# 1-Schematic_ESC36V_2_0.net
KiCad netlist of a schematic drawn in EasyEDA
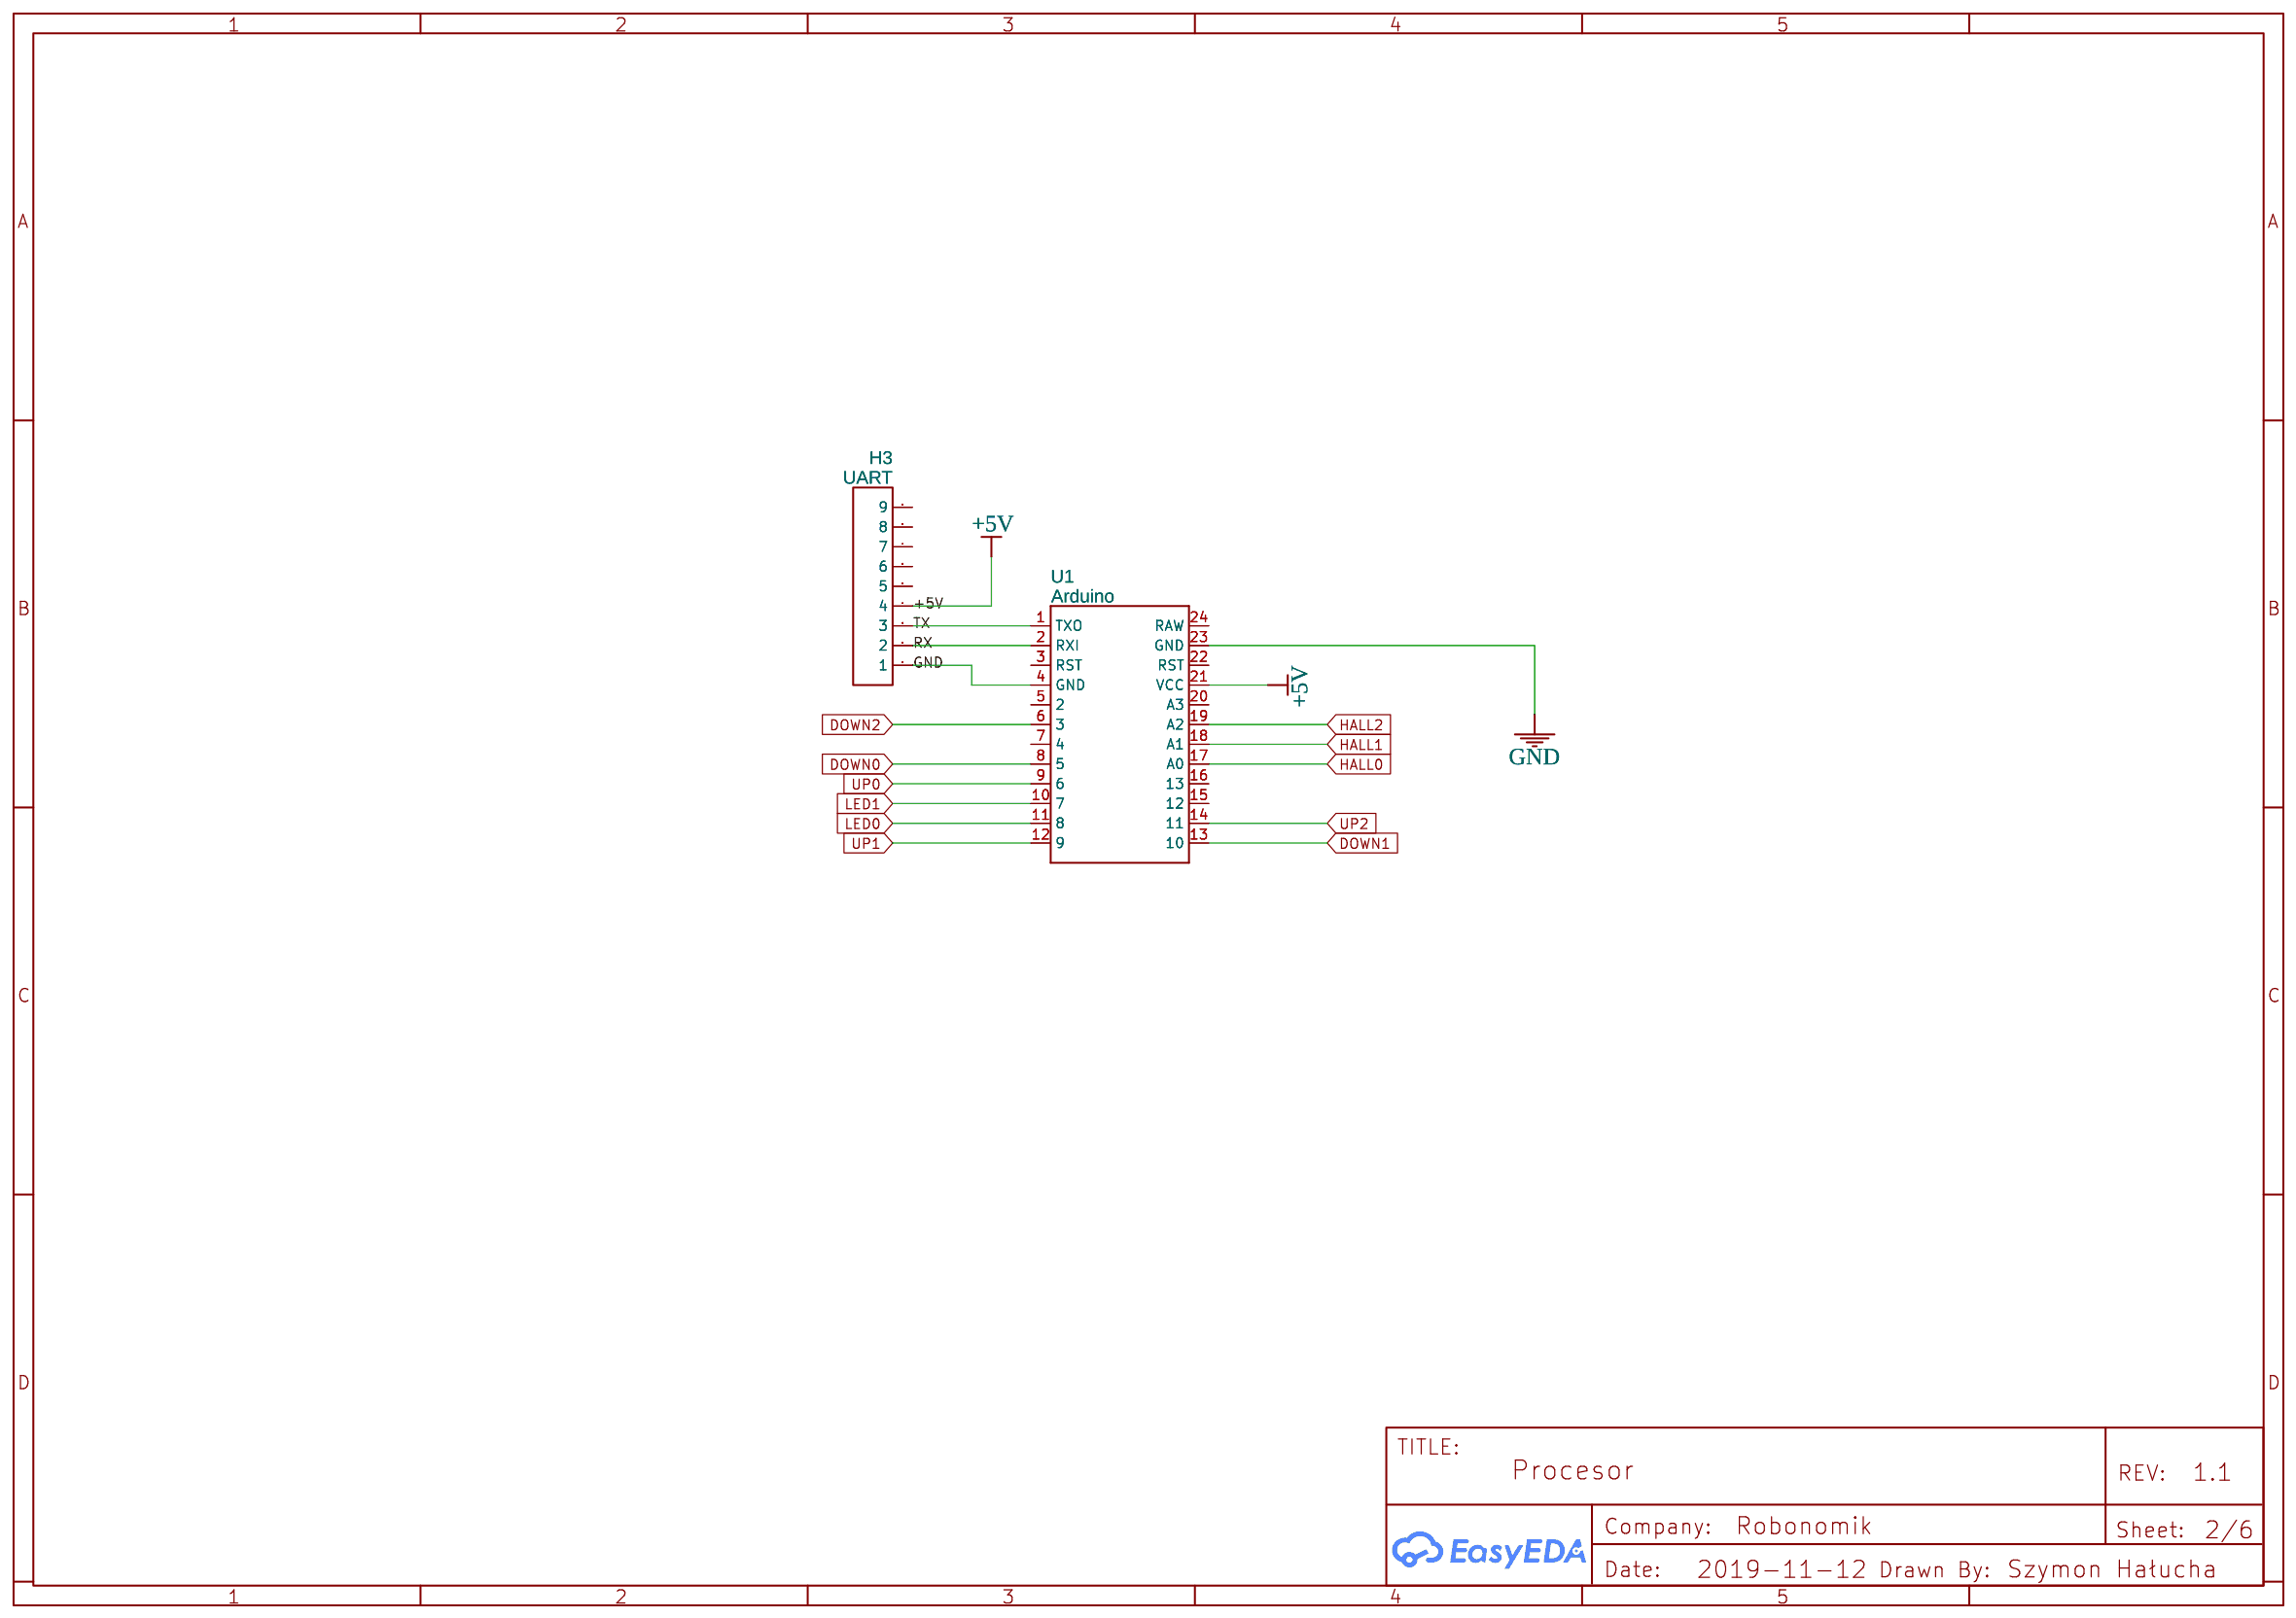
[diagram p0: Procesor]
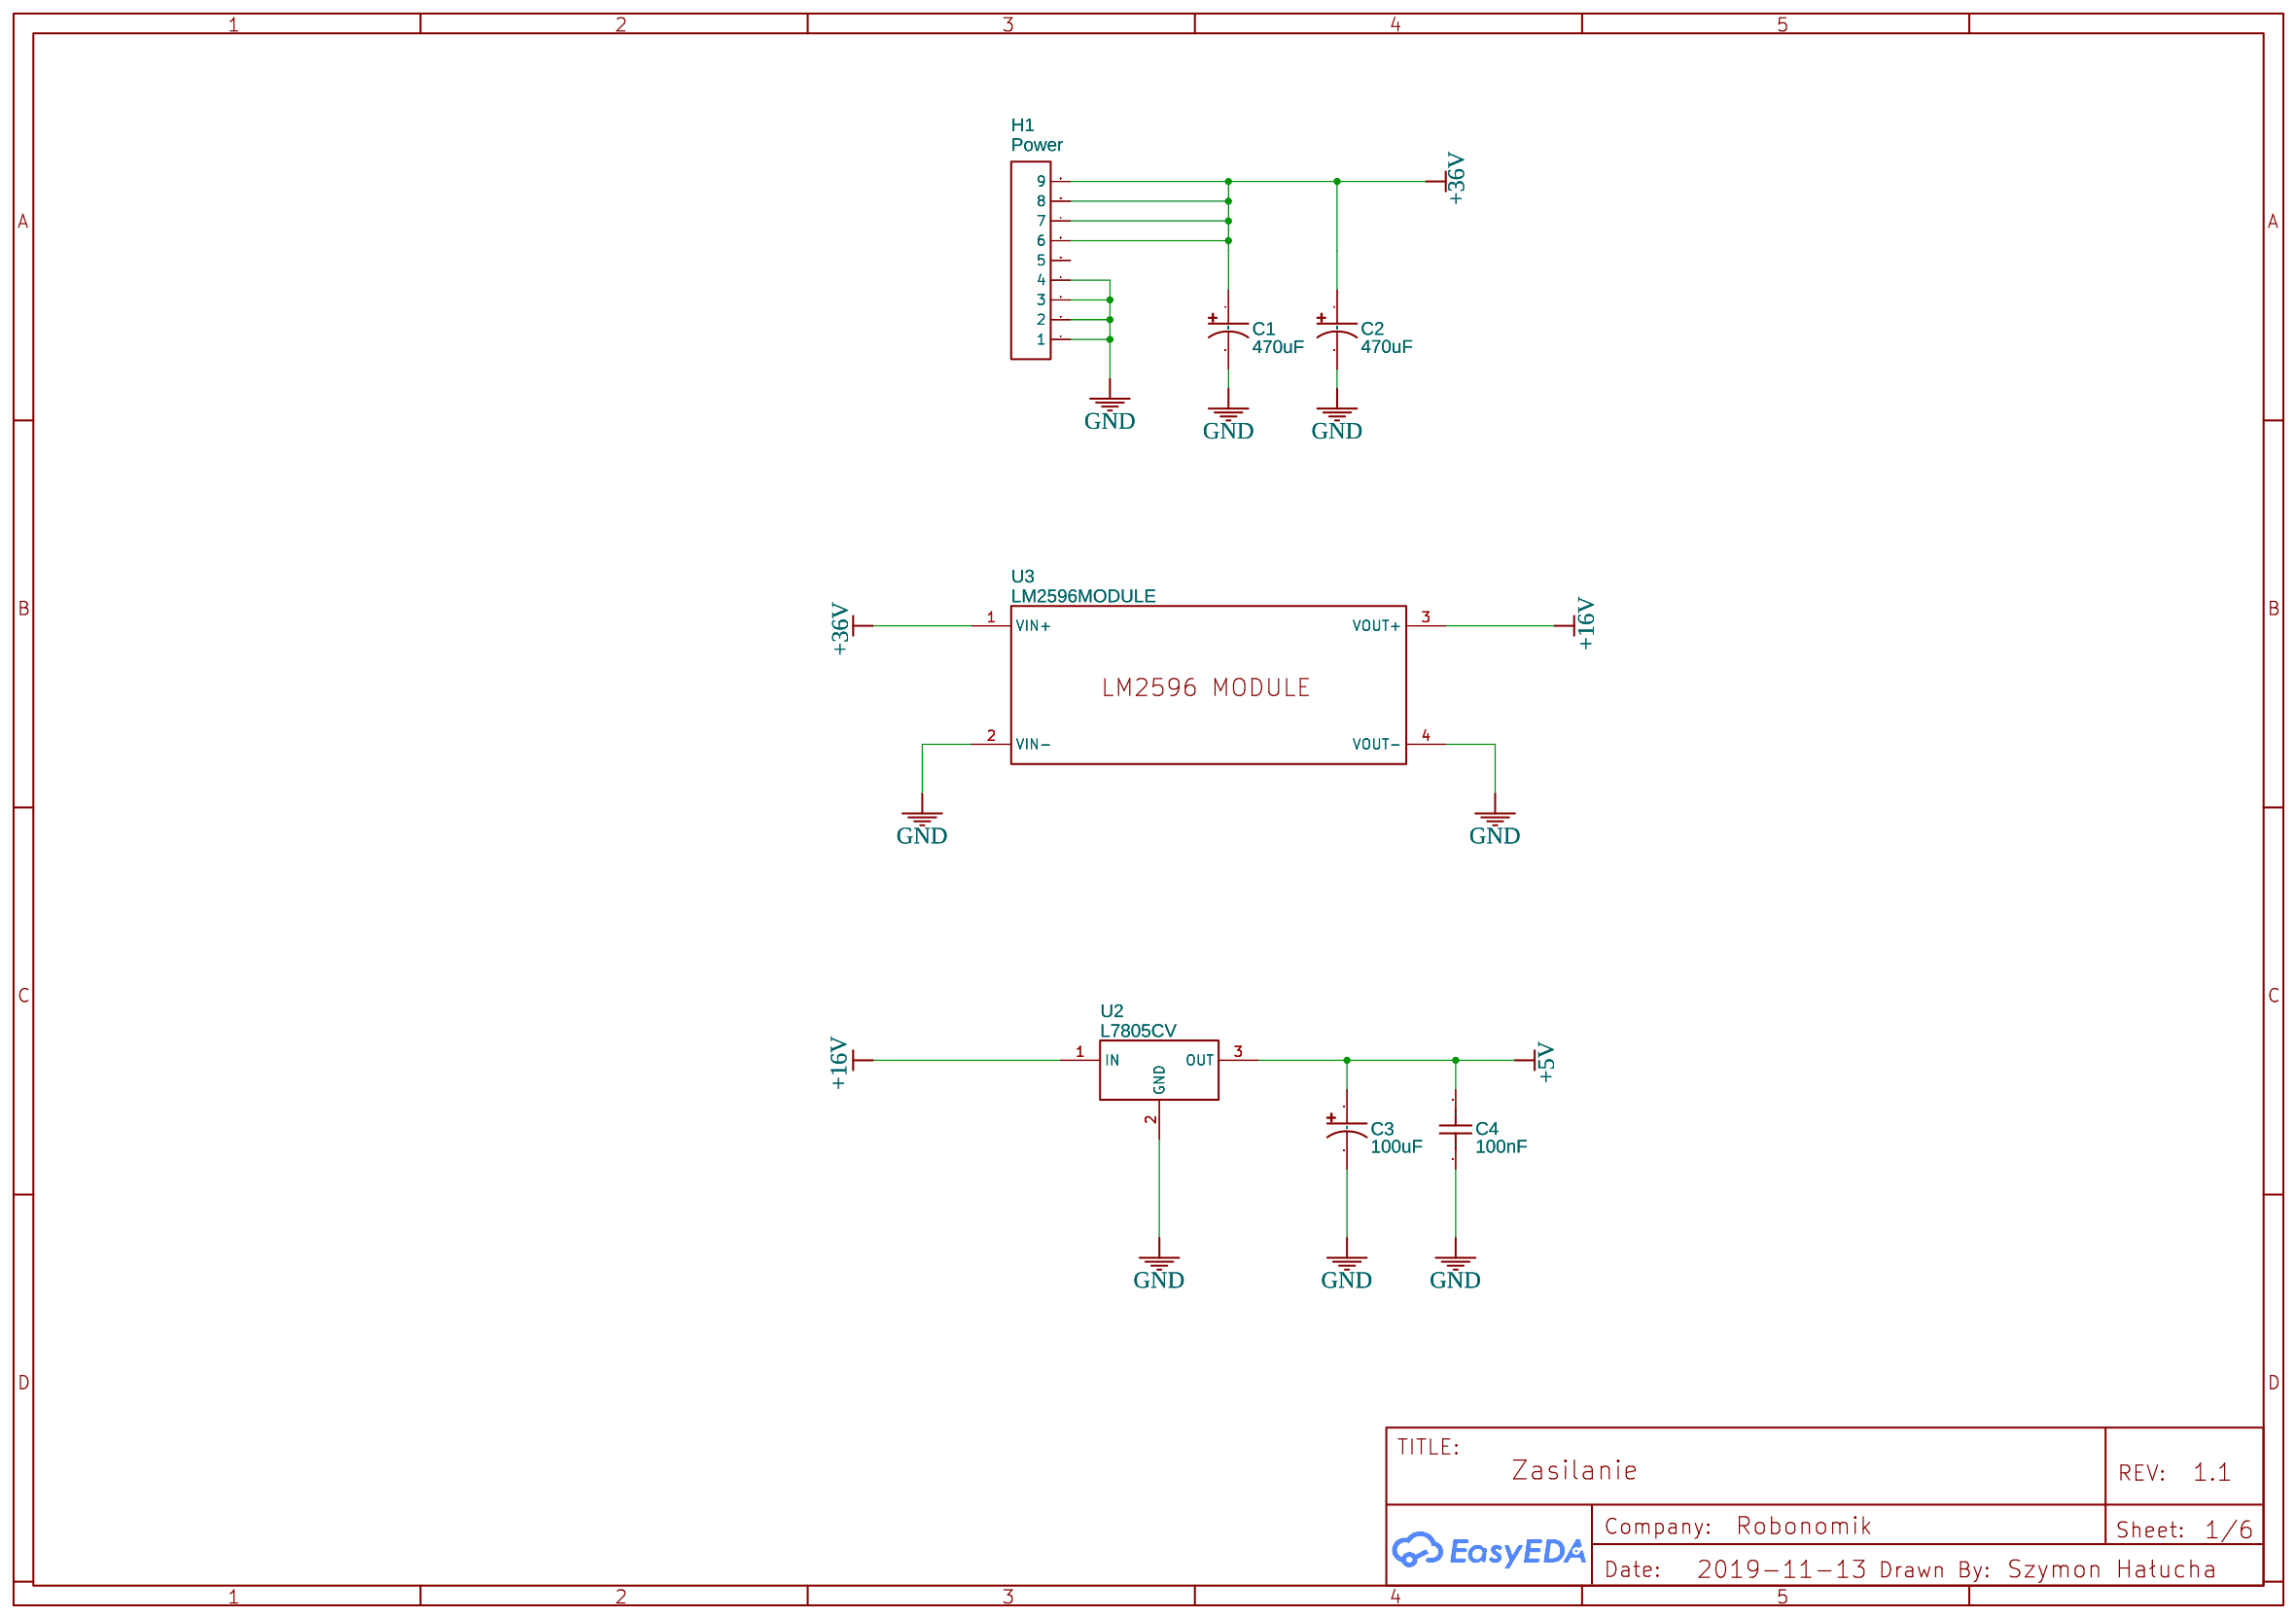
[diagram p1: Zasilanie]
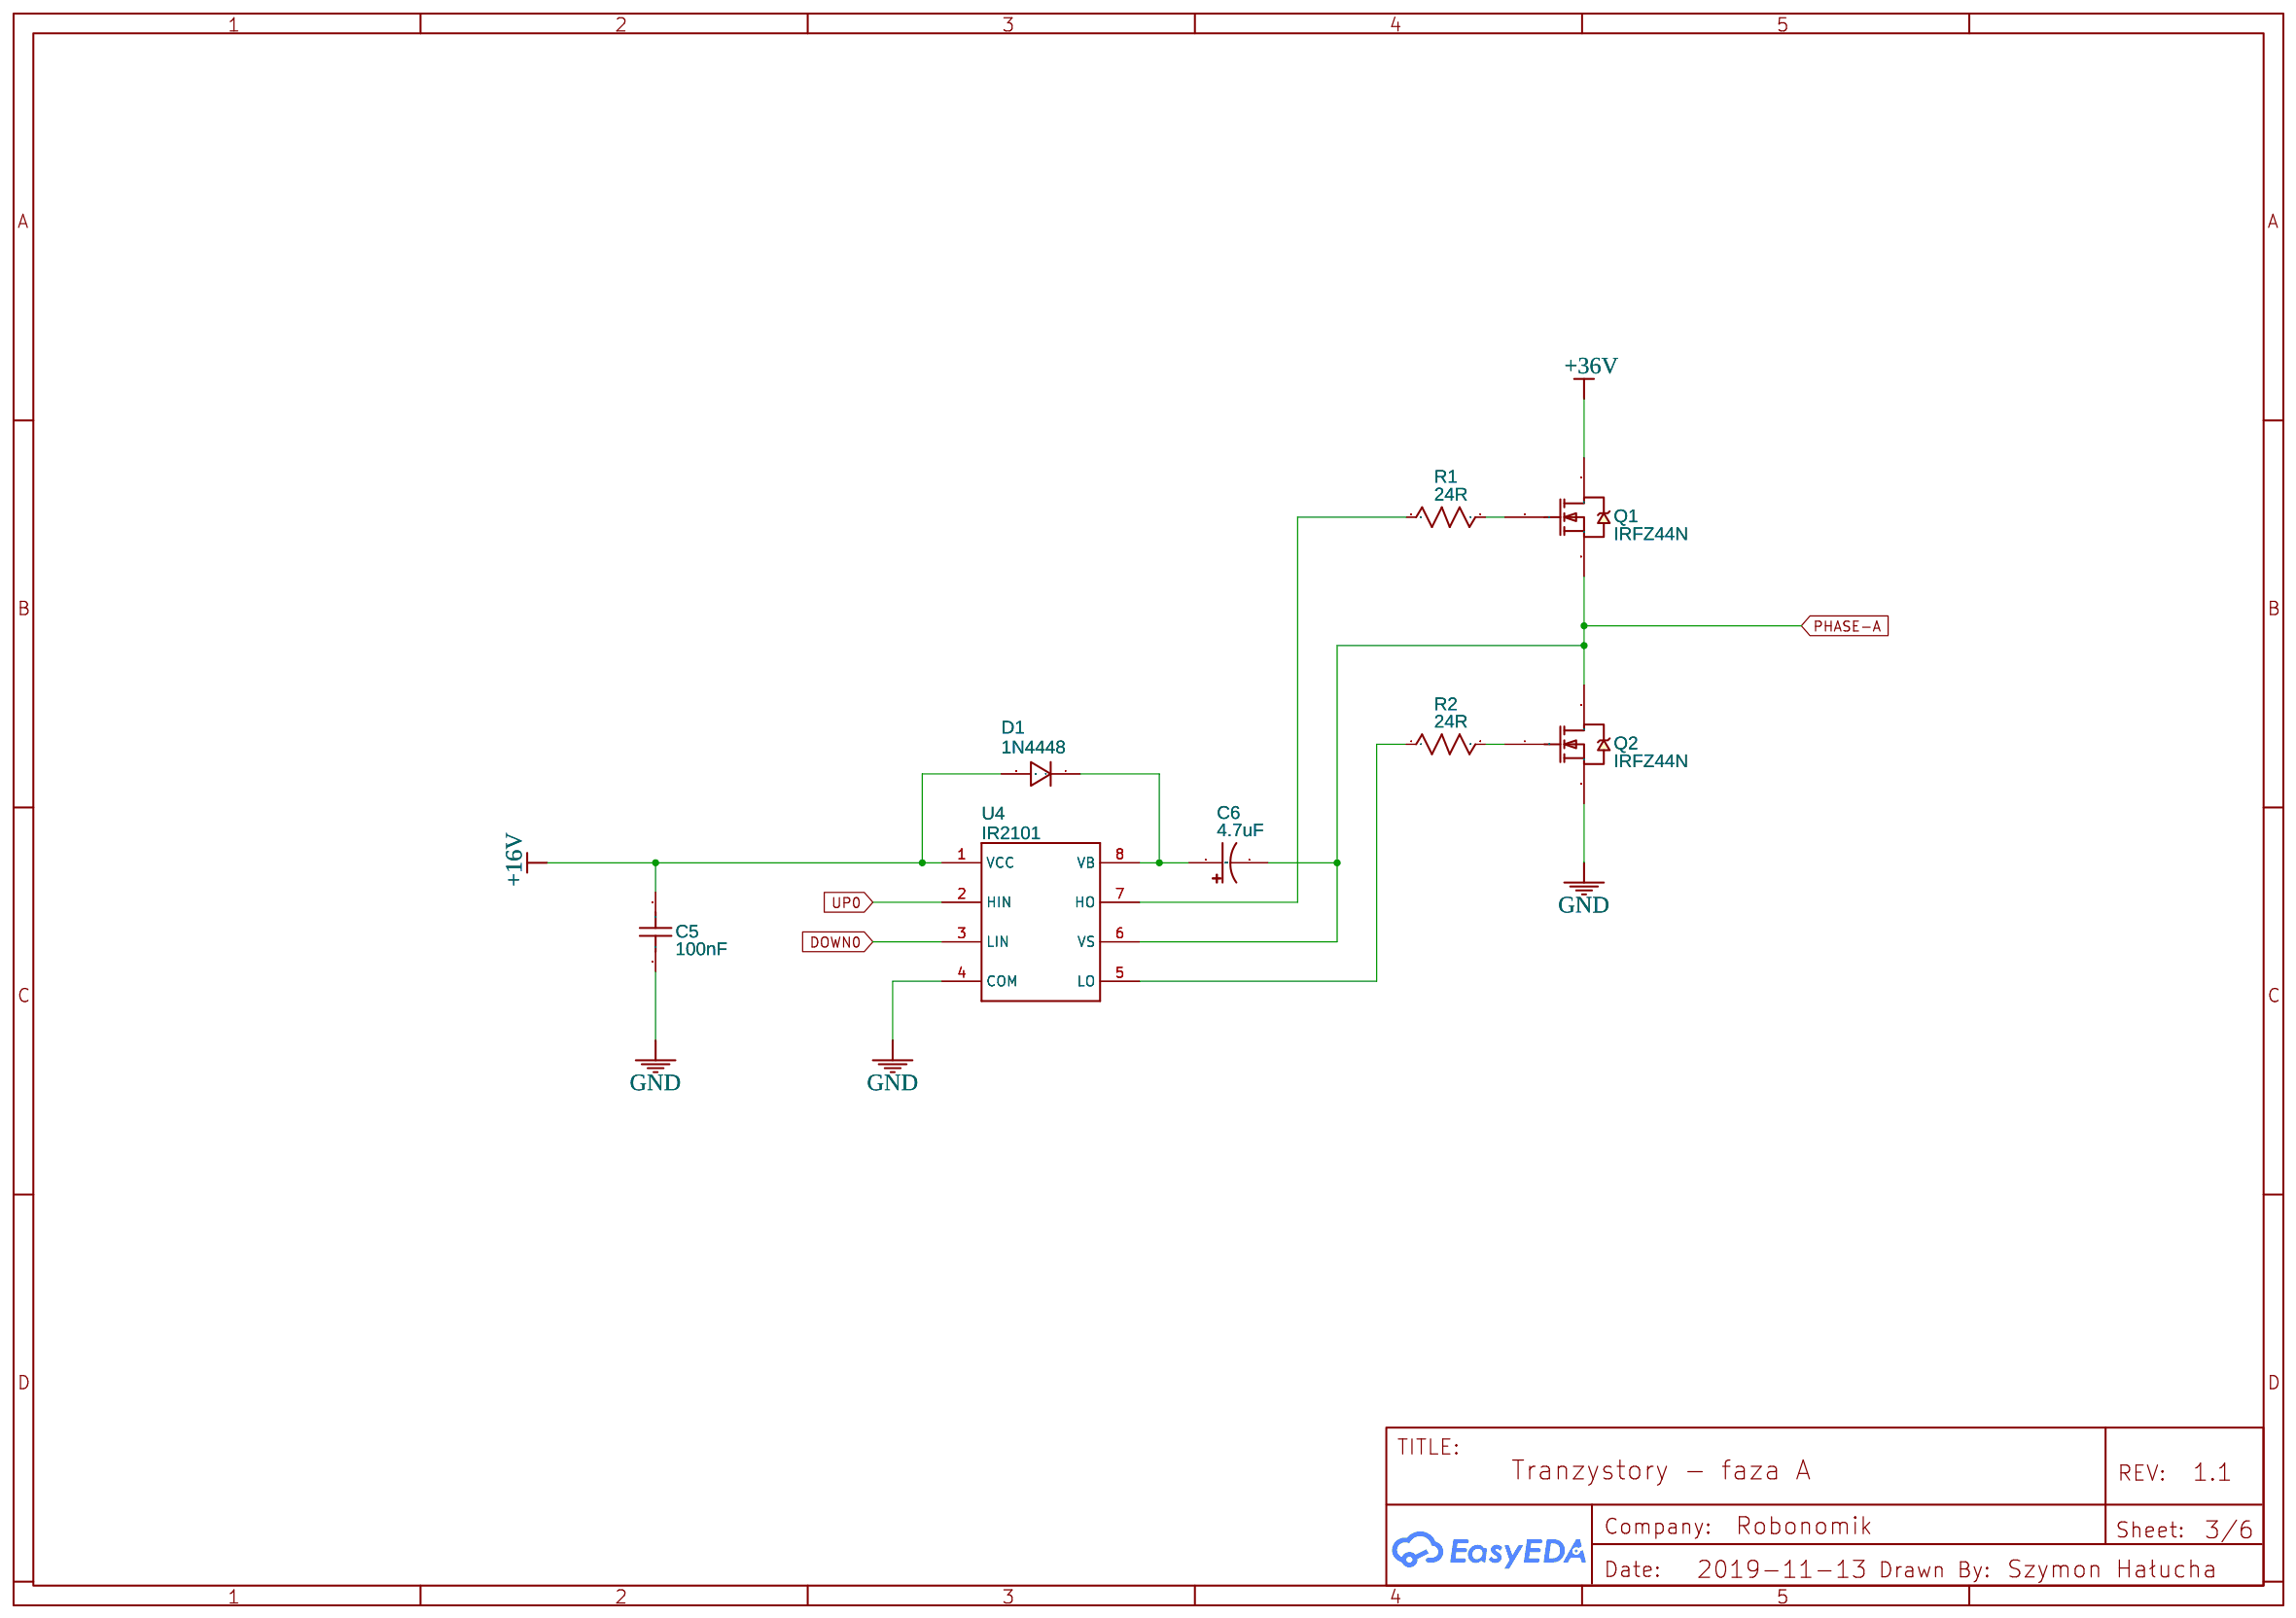
[diagram p2: TransA]
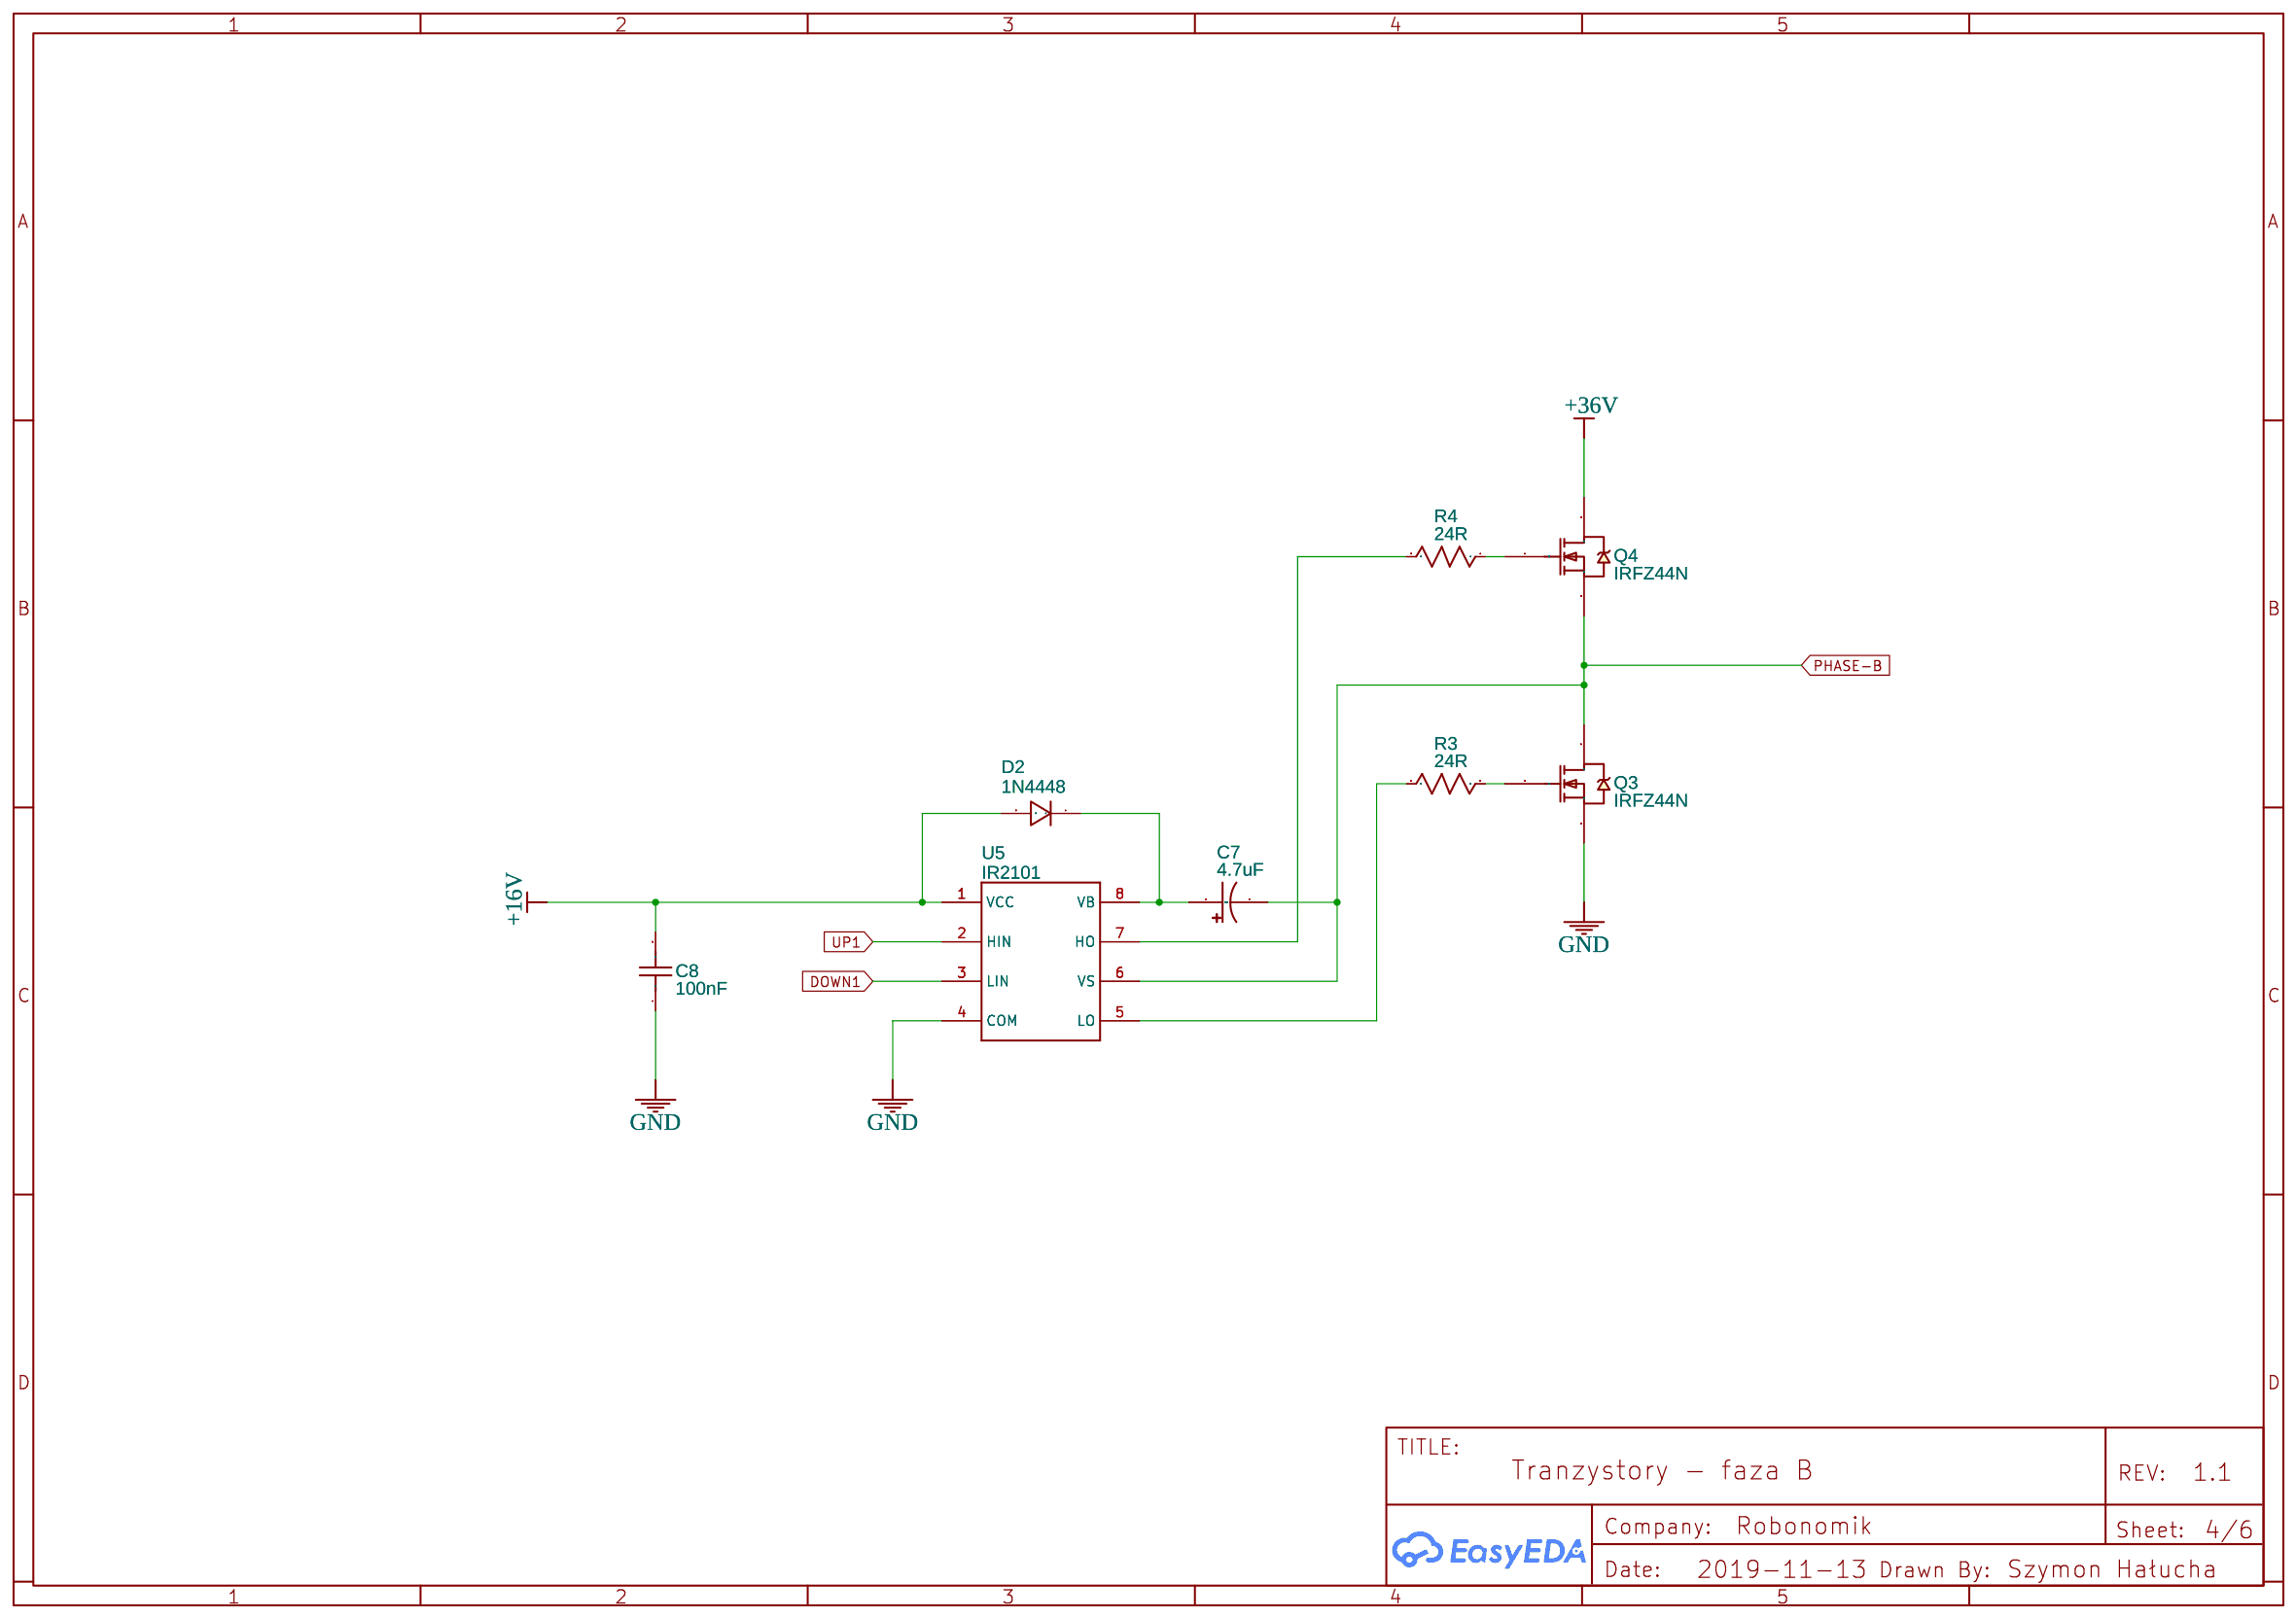
[diagram p3: TransB]
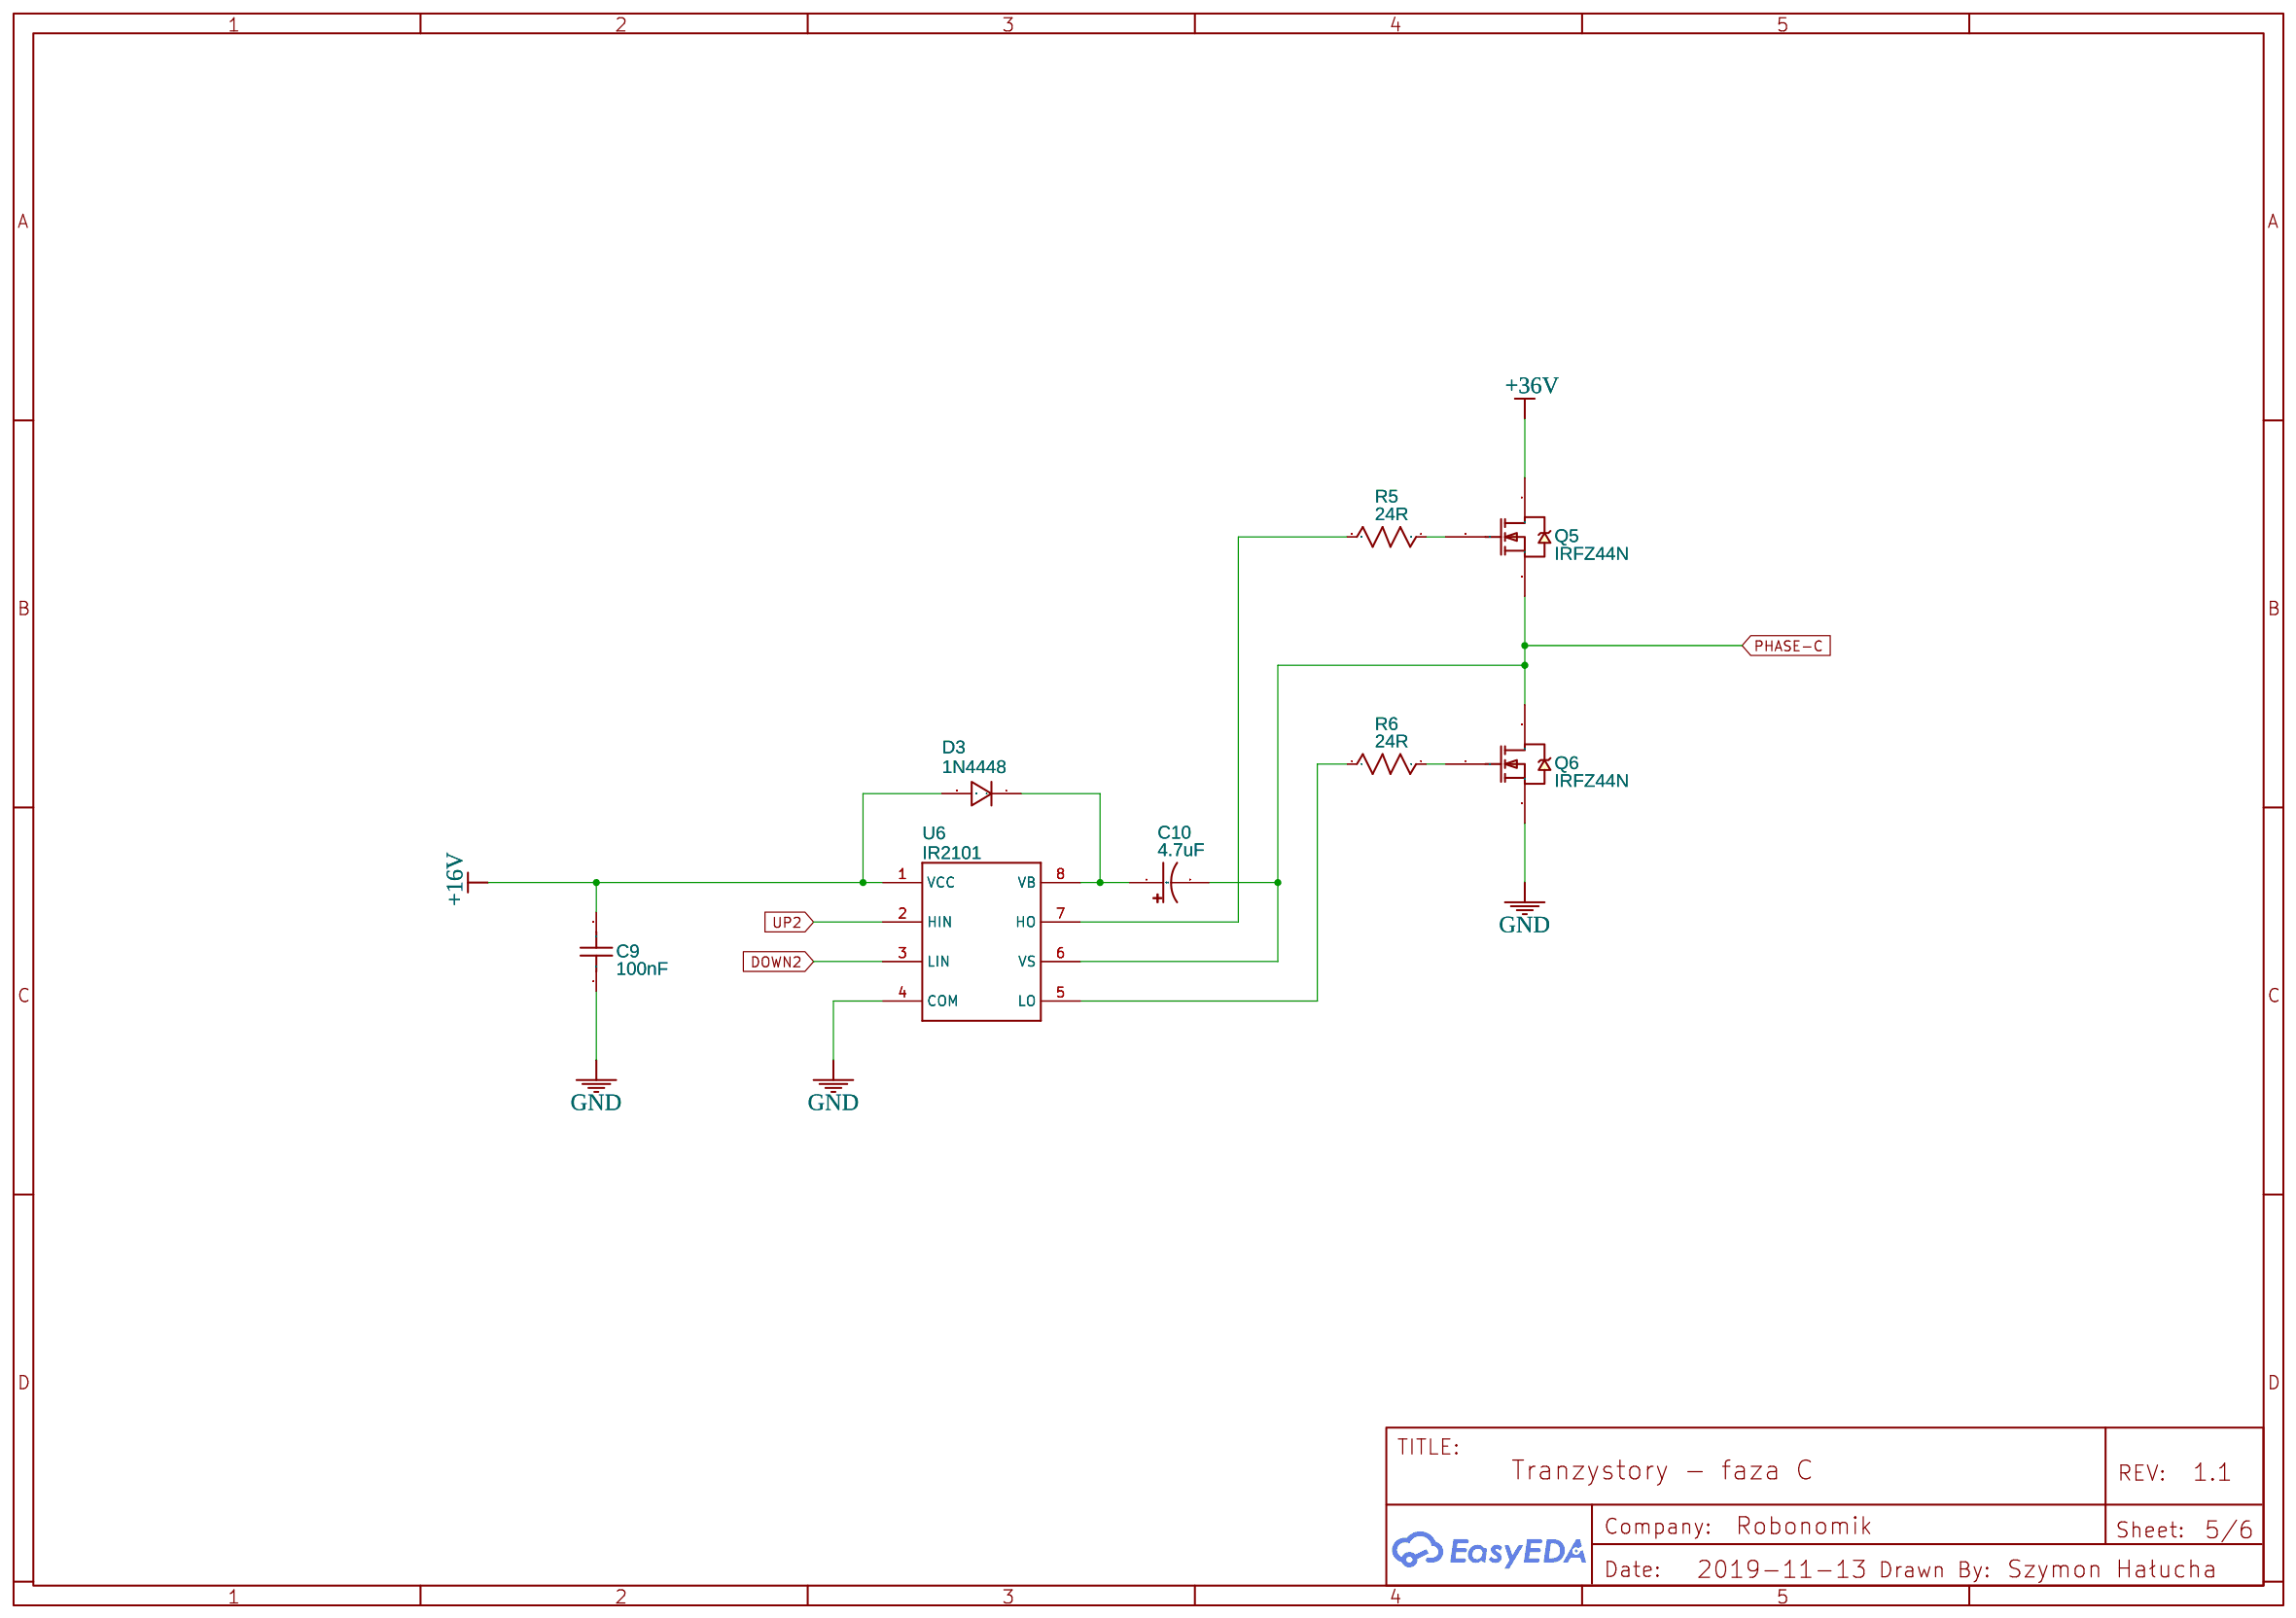
[diagram p4: TransC]
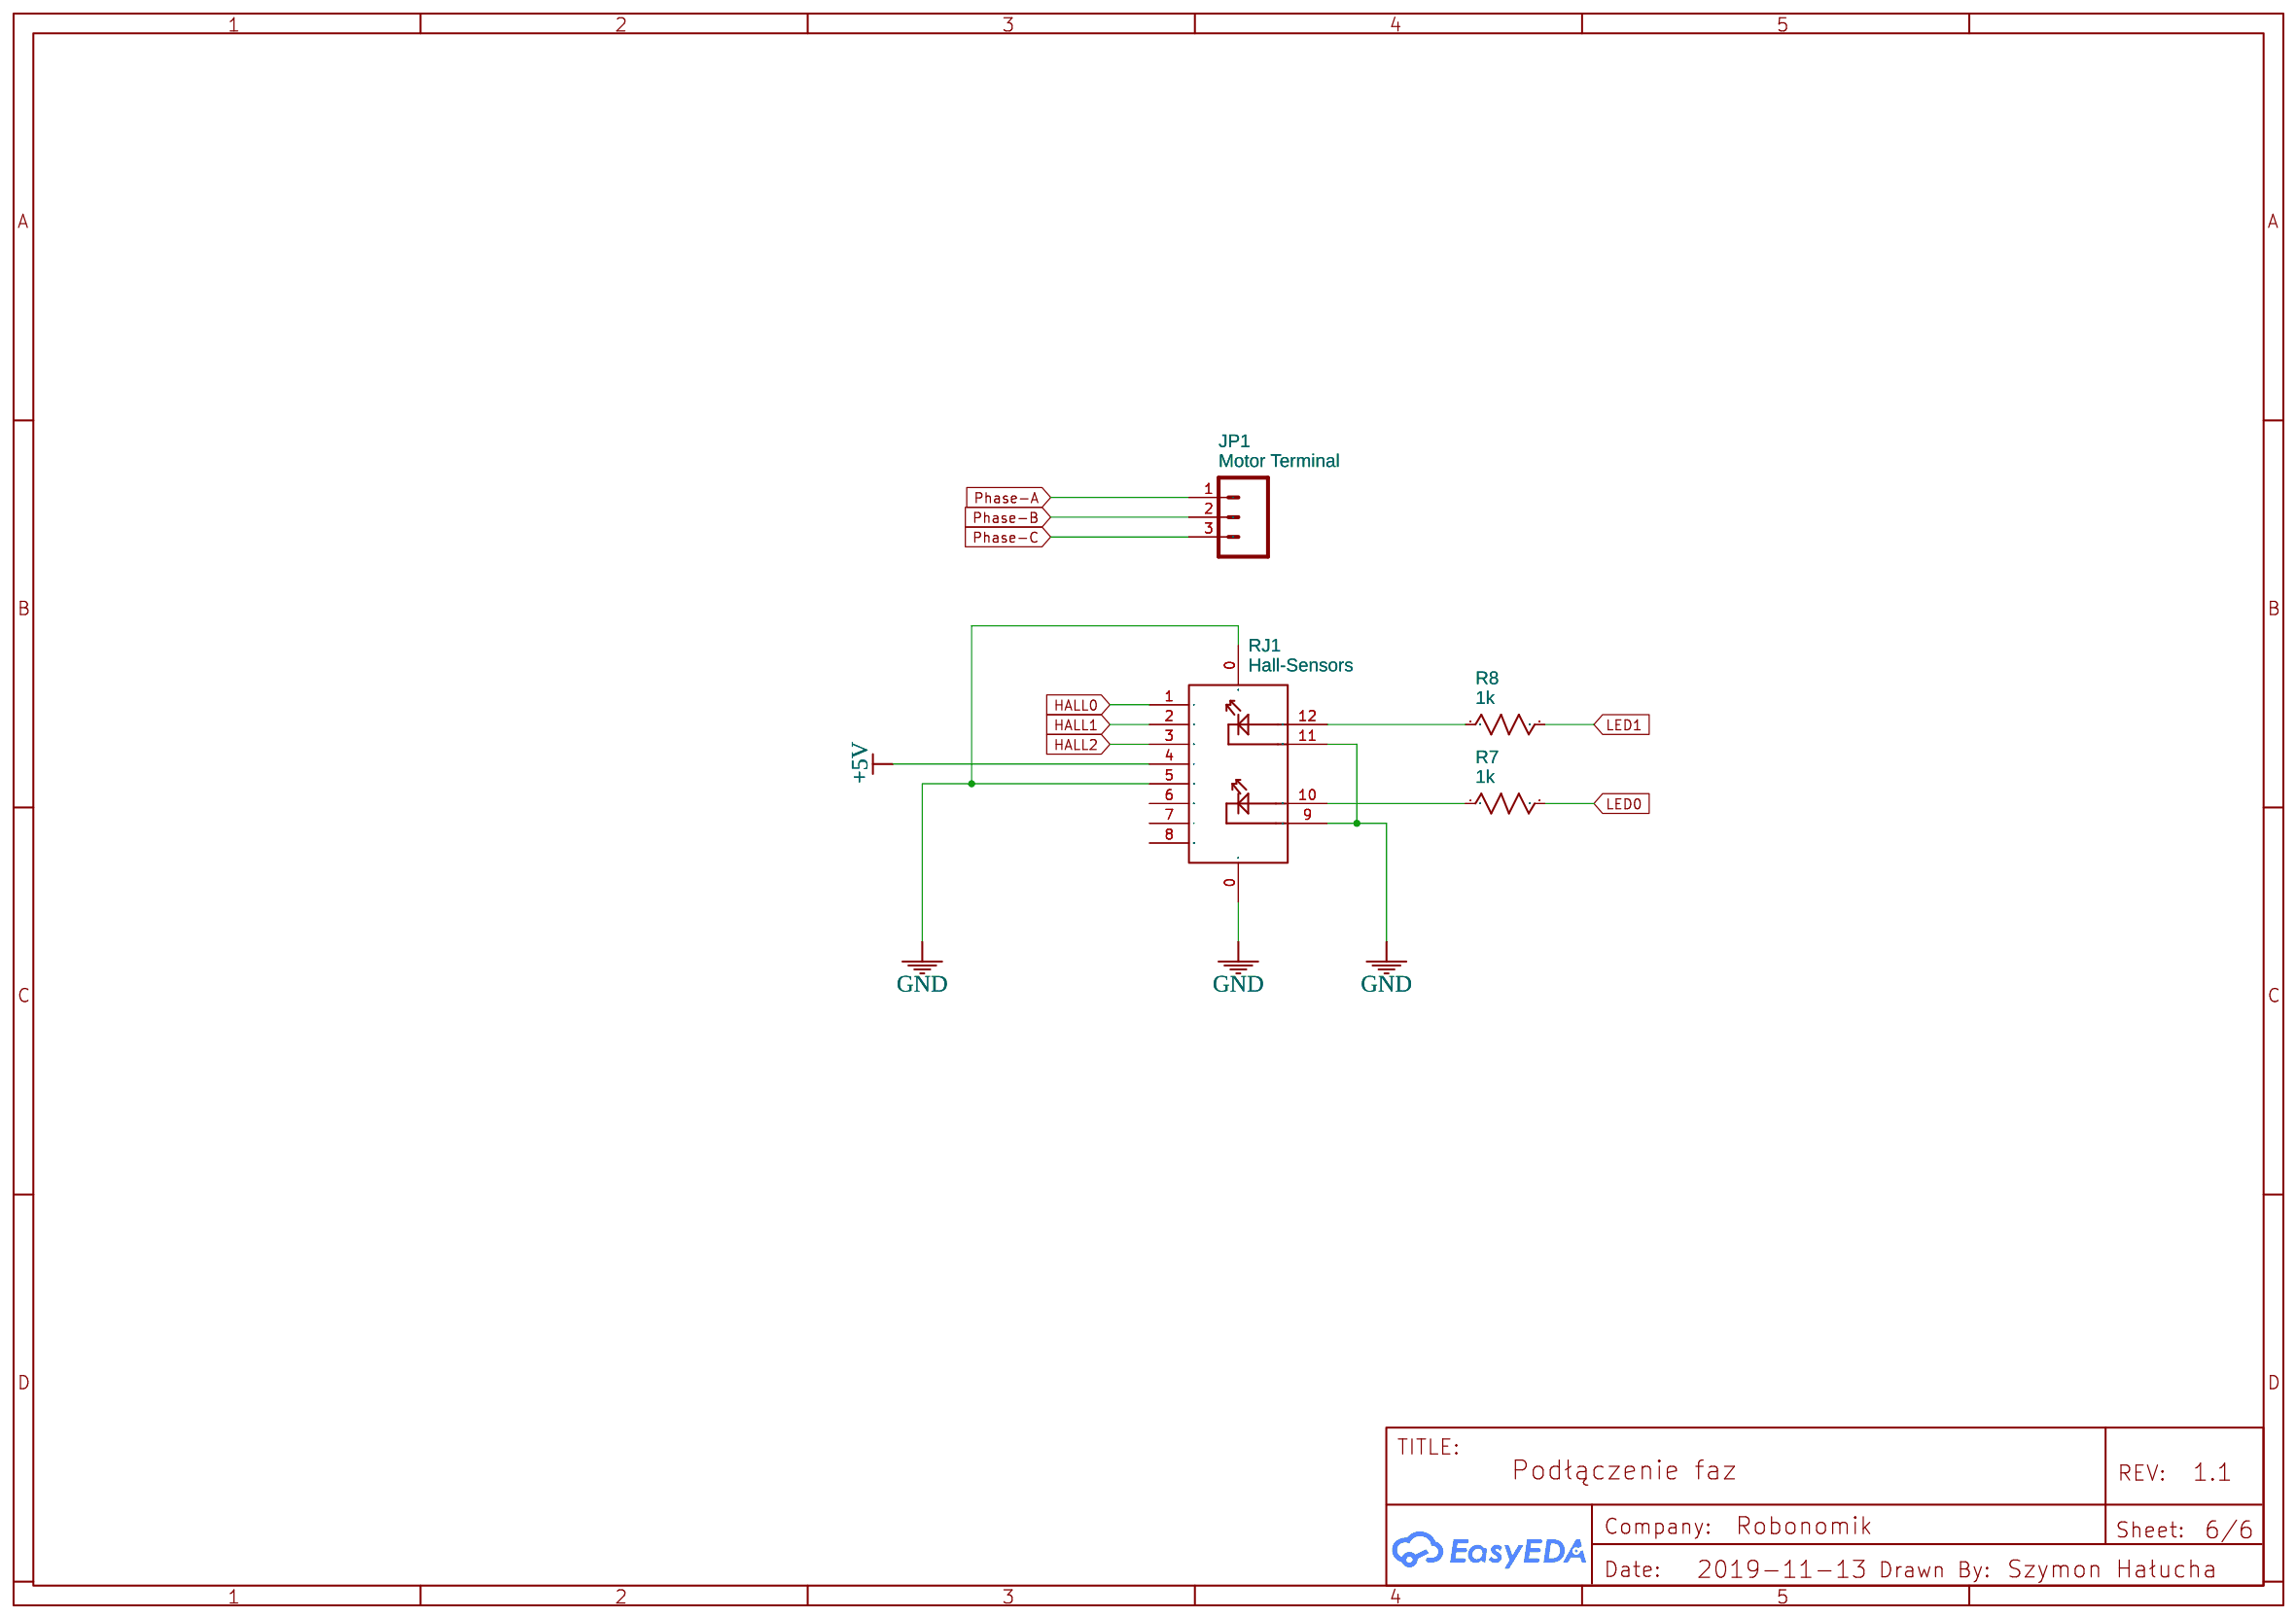
[diagram p5: Silnik]

(export (version "E")
  (design (tool "Eeschema 10.0.6"))
  (components
    (comp (ref "H3")
      (value "UART")
      (fields
        (field (name "BOM_Manufacturer Part") "2.54mm 1*9 Straight Female header")
        (field (name "BOM_Supplier Part") "C39576")
      )
      (libsource (lib "") (part "Unknown_440_290"))
    )
    (comp (ref "U1") (value "Arduino") (libsource (lib "") (part "Unknown_560_365")))
    (comp (ref "C1") (value "470uF") (libsource (lib "") (part "Cap_Electrolytic(TH)_D12.5XF5.0_US")))
    (comp (ref "C2") (value "470uF") (libsource (lib "") (part "Cap_Electrolytic(TH)_D12.5XF5.0_US")))
    (comp (ref "C3") (value "100uF") (libsource (lib "") (part "Cap_Electrolytic(TH)_D5.0XF2.0_US")))
    (comp (ref "C4") (value "100nF") (libsource (lib "") (part "Cap_RAD-0.1_US")))
    (comp (ref "H1")
      (value "Power")
      (fields
        (field (name "BOM_Manufacturer Part") "2.54mm 1*9 Straight Female header")
        (field (name "BOM_Supplier Part") "C39576")
      )
      (libsource (lib "") (part "Unknown_520_125"))
    )
    (comp (ref "U2")
      (value "L7805CV")
      (fields (field (name "BOM_Supplier Part") "C111887"))
      (libsource (lib "") (part "Unknown_580_545"))
    )
    (comp (ref "U3") (value "LM2596MODULE") (libsource (lib "") (part "Unknown_665_330")))
    (comp (ref "C5") (value "100nF") (libsource (lib "") (part "Cap_RAD-0.1_US")))
    (comp (ref "C6") (value "4.7uF") (libsource (lib "") (part "Cap_Electrolytic(TH)_D5.0XF2.0_US")))
    (comp (ref "D1")
      (value "1N4448")
      (fields (field (name "BOM_Supplier Part") "C258170"))
      (libsource (lib "") (part "Unknown_520_385"))
    )
    (comp (ref "Q1") (value "IRFZ44N") (libsource (lib "") (part "Unknown_780_255")))
    (comp (ref "Q2") (value "IRFZ44N") (libsource (lib "") (part "Unknown_780_370")))
    (comp (ref "R1") (value "24R") (libsource (lib "") (part "Res_AXIAL-0.4(1/4W)_US_1")))
    (comp (ref "R2") (value "24R") (libsource (lib "") (part "Res_AXIAL-0.4(1/4W)_US")))
    (comp (ref "U4") (value "IR2101") (libsource (lib "") (part "Unknown_520_460")))
    (comp (ref "C7") (value "4.7uF") (libsource (lib "") (part "Cap_Electrolytic(TH)_D5.0XF2.0_US")))
    (comp (ref "C8") (value "100nF") (libsource (lib "") (part "Cap_RAD-0.1_US")))
    (comp (ref "D2")
      (value "1N4448")
      (fields (field (name "BOM_Supplier Part") "C258170"))
      (libsource (lib "") (part "Unknown_520_405"))
    )
    (comp (ref "Q3") (value "IRFZ44N") (libsource (lib "") (part "Unknown_780_390")))
    (comp (ref "Q4") (value "IRFZ44N") (libsource (lib "") (part "Unknown_780_275")))
    (comp (ref "R3") (value "24R") (libsource (lib "") (part "Res_AXIAL-0.4(1/4W)_US")))
    (comp (ref "R4") (value "24R") (libsource (lib "") (part "Res_AXIAL-0.4(1/4W)_US_1")))
    (comp (ref "U5") (value "IR2101") (libsource (lib "") (part "Unknown_520_480")))
    (comp (ref "C9") (value "100nF") (libsource (lib "") (part "Cap_RAD-0.1_US")))
    (comp (ref "C10") (value "4.7uF") (libsource (lib "") (part "Cap_Electrolytic(TH)_D5.0XF2.0_US")))
    (comp (ref "D3")
      (value "1N4448")
      (fields (field (name "BOM_Supplier Part") "C258170"))
      (libsource (lib "") (part "Unknown_490_395"))
    )
    (comp (ref "Q5") (value "IRFZ44N") (libsource (lib "") (part "Unknown_750_265")))
    (comp (ref "Q6") (value "IRFZ44N") (libsource (lib "") (part "Unknown_750_380")))
    (comp (ref "R5") (value "24R") (libsource (lib "") (part "Res_AXIAL-0.4(1/4W)_US_1")))
    (comp (ref "R6") (value "24R") (libsource (lib "") (part "Res_AXIAL-0.4(1/4W)_US")))
    (comp (ref "U6") (value "IR2101") (libsource (lib "") (part "Unknown_490_470")))
    (comp (ref "JP1") (value "Motor Terminal") (libsource (lib "") (part "Unknown_615_255")))
    (comp (ref "R7") (value "1k") (libsource (lib "") (part "Res_AXIAL-0.4(1/4W)_US")))
    (comp (ref "R8") (value "1k") (libsource (lib "") (part "Res_AXIAL-0.4(1/4W)_US")))
    (comp (ref "RJ1")
      (value "Hall-Sensors")
      (fields
        (field (name "BOM_Manufacturer Part") "RJ45-B-1*1")
        (field (name "BOM_Supplier Part") "C138392")
      )
      (libsource (lib "") (part "Unknown_620_385"))
    )
  )
  (nets
    (net (code "1") (name "+5V") (class "Default")
      (node (ref "C3") (pin "1") (pinfunction "1_1") (pintype "unspecified"))
      (node (ref "C4") (pin "2") (pinfunction "2_2") (pintype "unspecified"))
      (node (ref "H3") (pin "4") (pinfunction "4_4") (pintype "input"))
      (node (ref "RJ1") (pin "4") (pinfunction "4_4") (pintype "unspecified"))
      (node (ref "U1") (pin "21") (pinfunction "VCC_21") (pintype "unspecified"))
      (node (ref "U2") (pin "3") (pinfunction "OUT_3") (pintype "passive"))
    )
    (net (code "2") (name "+16V") (class "Default")
      (node (ref "C5") (pin "2") (pinfunction "2_2") (pintype "unspecified"))
      (node (ref "C8") (pin "2") (pinfunction "2_2") (pintype "unspecified"))
      (node (ref "C9") (pin "2") (pinfunction "2_2") (pintype "unspecified"))
      (node (ref "D1") (pin "2") (pinfunction "2_2") (pintype "unspecified"))
      (node (ref "D2") (pin "2") (pinfunction "2_2") (pintype "unspecified"))
      (node (ref "D3") (pin "2") (pinfunction "2_2") (pintype "unspecified"))
      (node (ref "U2") (pin "1") (pinfunction "IN_1") (pintype "passive"))
      (node (ref "U3") (pin "3") (pinfunction "VOUT+_3") (pintype "unspecified"))
      (node (ref "U4") (pin "1") (pinfunction "VCC_1") (pintype "unspecified"))
      (node (ref "U5") (pin "1") (pinfunction "VCC_1") (pintype "unspecified"))
      (node (ref "U6") (pin "1") (pinfunction "VCC_1") (pintype "unspecified"))
    )
    (net (code "3") (name "+36V") (class "Default")
      (node (ref "C1") (pin "1") (pinfunction "1_1") (pintype "unspecified"))
      (node (ref "C2") (pin "1") (pinfunction "1_1") (pintype "unspecified"))
      (node (ref "H1") (pin "6") (pinfunction "6_6") (pintype "input"))
      (node (ref "H1") (pin "7") (pinfunction "7_7") (pintype "input"))
      (node (ref "H1") (pin "8") (pinfunction "8_8") (pintype "input"))
      (node (ref "H1") (pin "9") (pinfunction "9_9") (pintype "input"))
      (node (ref "Q1") (pin "2") (pinfunction "D_2") (pintype "unspecified"))
      (node (ref "Q4") (pin "2") (pinfunction "D_2") (pintype "unspecified"))
      (node (ref "Q5") (pin "2") (pinfunction "D_2") (pintype "unspecified"))
      (node (ref "U3") (pin "1") (pinfunction "VIN+_1") (pintype "unspecified"))
    )
    (net (code "4") (name "DOWN0") (class "Default")
      (node (ref "U1") (pin "8") (pinfunction "5_8") (pintype "unspecified"))
      (node (ref "U4") (pin "3") (pinfunction "LIN_3") (pintype "input"))
    )
    (net (code "5") (name "DOWN1") (class "Default")
      (node (ref "U1") (pin "13") (pinfunction "10_13") (pintype "unspecified"))
      (node (ref "U5") (pin "3") (pinfunction "LIN_3") (pintype "input"))
    )
    (net (code "6") (name "DOWN2") (class "Default")
      (node (ref "U1") (pin "6") (pinfunction "3_6") (pintype "unspecified"))
      (node (ref "U6") (pin "3") (pinfunction "LIN_3") (pintype "input"))
    )
    (net (code "7") (name "GND") (class "Default")
      (node (ref "C1") (pin "2") (pinfunction "2_2") (pintype "unspecified"))
      (node (ref "C2") (pin "2") (pinfunction "2_2") (pintype "unspecified"))
      (node (ref "C3") (pin "2") (pinfunction "2_2") (pintype "unspecified"))
      (node (ref "C4") (pin "1") (pinfunction "1_1") (pintype "unspecified"))
      (node (ref "C5") (pin "1") (pinfunction "1_1") (pintype "unspecified"))
      (node (ref "C8") (pin "1") (pinfunction "1_1") (pintype "unspecified"))
      (node (ref "C9") (pin "1") (pinfunction "1_1") (pintype "unspecified"))
      (node (ref "H1") (pin "1") (pinfunction "1_1") (pintype "input"))
      (node (ref "H1") (pin "2") (pinfunction "2_2") (pintype "input"))
      (node (ref "H1") (pin "3") (pinfunction "3_3") (pintype "input"))
      (node (ref "H1") (pin "4") (pinfunction "4_4") (pintype "input"))
      (node (ref "H3") (pin "1") (pinfunction "1_1") (pintype "input"))
      (node (ref "Q2") (pin "3") (pinfunction "S_3") (pintype "unspecified"))
      (node (ref "Q3") (pin "3") (pinfunction "S_3") (pintype "unspecified"))
      (node (ref "Q6") (pin "3") (pinfunction "S_3") (pintype "unspecified"))
      (node (ref "RJ1") (pin "0") (pinfunction "S_0") (pintype "unspecified"))
      (node (ref "RJ1") (pin "11") (pinfunction "11_11") (pintype "unspecified"))
      (node (ref "RJ1") (pin "5") (pinfunction "5_5") (pintype "unspecified"))
      (node (ref "RJ1") (pin "9") (pinfunction "9_9") (pintype "unspecified"))
      (node (ref "U1") (pin "23") (pinfunction "GND_23") (pintype "unspecified"))
      (node (ref "U1") (pin "4") (pinfunction "GND_4") (pintype "unspecified"))
      (node (ref "U2") (pin "2") (pinfunction "GND_2") (pintype "passive"))
      (node (ref "U3") (pin "2") (pinfunction "VIN-_2") (pintype "unspecified"))
      (node (ref "U3") (pin "4") (pinfunction "VOUT-_4") (pintype "unspecified"))
      (node (ref "U4") (pin "4") (pinfunction "COM_4") (pintype "unspecified"))
      (node (ref "U5") (pin "4") (pinfunction "COM_4") (pintype "unspecified"))
      (node (ref "U6") (pin "4") (pinfunction "COM_4") (pintype "unspecified"))
    )
    (net (code "8") (name "HALL0") (class "Default")
      (node (ref "RJ1") (pin "1") (pinfunction "1_1") (pintype "unspecified"))
      (node (ref "U1") (pin "17") (pinfunction "A0_17") (pintype "unspecified"))
    )
    (net (code "9") (name "HALL1") (class "Default")
      (node (ref "RJ1") (pin "2") (pinfunction "2_2") (pintype "unspecified"))
      (node (ref "U1") (pin "18") (pinfunction "A1_18") (pintype "unspecified"))
    )
    (net (code "10") (name "HALL2") (class "Default")
      (node (ref "RJ1") (pin "3") (pinfunction "3_3") (pintype "unspecified"))
      (node (ref "U1") (pin "19") (pinfunction "A2_19") (pintype "unspecified"))
    )
    (net (code "11") (name "LED0") (class "Default")
      (node (ref "R7") (pin "2") (pinfunction "2_2") (pintype "unspecified"))
      (node (ref "U1") (pin "11") (pinfunction "8_11") (pintype "unspecified"))
    )
    (net (code "12") (name "LED1") (class "Default")
      (node (ref "R8") (pin "2") (pinfunction "2_2") (pintype "unspecified"))
      (node (ref "U1") (pin "10") (pinfunction "7_10") (pintype "unspecified"))
    )
    (net (code "13") (name "Net-(Q1-G)") (class "Default")
      (node (ref "Q1") (pin "1") (pinfunction "G_1") (pintype "unspecified"))
      (node (ref "R1") (pin "1") (pinfunction "1_1") (pintype "unspecified"))
    )
    (net (code "14") (name "Net-(Q2-G)") (class "Default")
      (node (ref "Q2") (pin "1") (pinfunction "G_1") (pintype "unspecified"))
      (node (ref "R2") (pin "2") (pinfunction "2_2") (pintype "unspecified"))
    )
    (net (code "15") (name "Net-(Q3-G)") (class "Default")
      (node (ref "Q3") (pin "1") (pinfunction "G_1") (pintype "unspecified"))
      (node (ref "R3") (pin "2") (pinfunction "2_2") (pintype "unspecified"))
    )
    (net (code "16") (name "Net-(Q4-G)") (class "Default")
      (node (ref "Q4") (pin "1") (pinfunction "G_1") (pintype "unspecified"))
      (node (ref "R4") (pin "1") (pinfunction "1_1") (pintype "unspecified"))
    )
    (net (code "17") (name "Net-(Q5-G)") (class "Default")
      (node (ref "Q5") (pin "1") (pinfunction "G_1") (pintype "unspecified"))
      (node (ref "R5") (pin "1") (pinfunction "1_1") (pintype "unspecified"))
    )
    (net (code "18") (name "Net-(Q6-G)") (class "Default")
      (node (ref "Q6") (pin "1") (pinfunction "G_1") (pintype "unspecified"))
      (node (ref "R6") (pin "2") (pinfunction "2_2") (pintype "unspecified"))
    )
    (net (code "19") (name "Net-(R7-Pad1)") (class "Default")
      (node (ref "R7") (pin "1") (pinfunction "1_1") (pintype "unspecified"))
      (node (ref "RJ1") (pin "10") (pinfunction "10_10") (pintype "unspecified"))
    )
    (net (code "20") (name "Net-(R8-Pad1)") (class "Default")
      (node (ref "R8") (pin "1") (pinfunction "1_1") (pintype "unspecified"))
      (node (ref "RJ1") (pin "12") (pinfunction "12_12") (pintype "unspecified"))
    )
    (net (code "21") (name "Net-(U4-HO)") (class "Default")
      (node (ref "R1") (pin "2") (pinfunction "2_2") (pintype "unspecified"))
      (node (ref "U4") (pin "7") (pinfunction "HO_7") (pintype "output"))
    )
    (net (code "22") (name "Net-(U4-LO)") (class "Default")
      (node (ref "R2") (pin "1") (pinfunction "1_1") (pintype "unspecified"))
      (node (ref "U4") (pin "5") (pinfunction "LO_5") (pintype "output"))
    )
    (net (code "23") (name "Net-(U4-VB)") (class "Default")
      (node (ref "C6") (pin "1") (pinfunction "1_1") (pintype "unspecified"))
      (node (ref "D1") (pin "1") (pinfunction "1_1") (pintype "unspecified"))
      (node (ref "U4") (pin "8") (pinfunction "VB_8") (pintype "unspecified"))
    )
    (net (code "24") (name "Net-(U5-HO)") (class "Default")
      (node (ref "R4") (pin "2") (pinfunction "2_2") (pintype "unspecified"))
      (node (ref "U5") (pin "7") (pinfunction "HO_7") (pintype "output"))
    )
    (net (code "25") (name "Net-(U5-LO)") (class "Default")
      (node (ref "R3") (pin "1") (pinfunction "1_1") (pintype "unspecified"))
      (node (ref "U5") (pin "5") (pinfunction "LO_5") (pintype "output"))
    )
    (net (code "26") (name "Net-(U5-VB)") (class "Default")
      (node (ref "C7") (pin "1") (pinfunction "1_1") (pintype "unspecified"))
      (node (ref "D2") (pin "1") (pinfunction "1_1") (pintype "unspecified"))
      (node (ref "U5") (pin "8") (pinfunction "VB_8") (pintype "unspecified"))
    )
    (net (code "27") (name "Net-(U6-HO)") (class "Default")
      (node (ref "R5") (pin "2") (pinfunction "2_2") (pintype "unspecified"))
      (node (ref "U6") (pin "7") (pinfunction "HO_7") (pintype "output"))
    )
    (net (code "28") (name "Net-(U6-LO)") (class "Default")
      (node (ref "R6") (pin "1") (pinfunction "1_1") (pintype "unspecified"))
      (node (ref "U6") (pin "5") (pinfunction "LO_5") (pintype "output"))
    )
    (net (code "29") (name "Net-(U6-VB)") (class "Default")
      (node (ref "C10") (pin "1") (pinfunction "1_1") (pintype "unspecified"))
      (node (ref "D3") (pin "1") (pinfunction "1_1") (pintype "unspecified"))
      (node (ref "U6") (pin "8") (pinfunction "VB_8") (pintype "unspecified"))
    )
    (net (code "30") (name "PHASE-A") (class "Default")
      (node (ref "C6") (pin "2") (pinfunction "2_2") (pintype "unspecified"))
      (node (ref "Q1") (pin "3") (pinfunction "S_3") (pintype "unspecified"))
      (node (ref "Q2") (pin "2") (pinfunction "D_2") (pintype "unspecified"))
      (node (ref "U4") (pin "6") (pinfunction "VS_6") (pintype "output"))
    )
    (net (code "31") (name "PHASE-B") (class "Default")
      (node (ref "C7") (pin "2") (pinfunction "2_2") (pintype "unspecified"))
      (node (ref "Q3") (pin "2") (pinfunction "D_2") (pintype "unspecified"))
      (node (ref "Q4") (pin "3") (pinfunction "S_3") (pintype "unspecified"))
      (node (ref "U5") (pin "6") (pinfunction "VS_6") (pintype "output"))
    )
    (net (code "32") (name "PHASE-C") (class "Default")
      (node (ref "C10") (pin "2") (pinfunction "2_2") (pintype "unspecified"))
      (node (ref "Q5") (pin "3") (pinfunction "S_3") (pintype "unspecified"))
      (node (ref "Q6") (pin "2") (pinfunction "D_2") (pintype "unspecified"))
      (node (ref "U6") (pin "6") (pinfunction "VS_6") (pintype "output"))
    )
    (net (code "33") (name "Phase-A") (class "Default")
      (node (ref "JP1") (pin "1") (pinfunction "1_1") (pintype "unspecified"))
    )
    (net (code "34") (name "Phase-B") (class "Default")
      (node (ref "JP1") (pin "2") (pinfunction "2_2") (pintype "unspecified"))
    )
    (net (code "35") (name "Phase-C") (class "Default")
      (node (ref "JP1") (pin "3") (pinfunction "3_3") (pintype "unspecified"))
    )
    (net (code "36") (name "RX") (class "Default")
      (node (ref "H3") (pin "2") (pinfunction "2_2") (pintype "input"))
      (node (ref "U1") (pin "2") (pinfunction "RXI_2") (pintype "unspecified"))
    )
    (net (code "37") (name "TX") (class "Default")
      (node (ref "H3") (pin "3") (pinfunction "3_3") (pintype "input"))
      (node (ref "U1") (pin "1") (pinfunction "TXO_1") (pintype "unspecified"))
    )
    (net (code "38") (name "UP0") (class "Default")
      (node (ref "U1") (pin "9") (pinfunction "6_9") (pintype "unspecified"))
      (node (ref "U4") (pin "2") (pinfunction "HIN_2") (pintype "input"))
    )
    (net (code "39") (name "UP1") (class "Default")
      (node (ref "U1") (pin "12") (pinfunction "9_12") (pintype "unspecified"))
      (node (ref "U5") (pin "2") (pinfunction "HIN_2") (pintype "input"))
    )
    (net (code "40") (name "UP2") (class "Default")
      (node (ref "U1") (pin "14") (pinfunction "11_14") (pintype "unspecified"))
      (node (ref "U6") (pin "2") (pinfunction "HIN_2") (pintype "input"))
    )
    (net (code "41") (name "unconnected-(H1-Pad5)") (class "Default")
      (node (ref "H1") (pin "5") (pinfunction "5_5") (pintype "input"))
    )
    (net (code "42") (name "unconnected-(H3-Pad5)") (class "Default")
      (node (ref "H3") (pin "5") (pinfunction "5_5") (pintype "input"))
    )
    (net (code "43") (name "unconnected-(H3-Pad6)") (class "Default")
      (node (ref "H3") (pin "6") (pinfunction "6_6") (pintype "input"))
    )
    (net (code "44") (name "unconnected-(H3-Pad7)") (class "Default")
      (node (ref "H3") (pin "7") (pinfunction "7_7") (pintype "input"))
    )
    (net (code "45") (name "unconnected-(H3-Pad8)") (class "Default")
      (node (ref "H3") (pin "8") (pinfunction "8_8") (pintype "input"))
    )
    (net (code "46") (name "unconnected-(H3-Pad9)") (class "Default")
      (node (ref "H3") (pin "9") (pinfunction "9_9") (pintype "input"))
    )
    (net (code "47") (name "unconnected-(RJ1-Pad6)") (class "Default")
      (node (ref "RJ1") (pin "6") (pinfunction "6_6") (pintype "unspecified"))
    )
    (net (code "48") (name "unconnected-(RJ1-Pad7)") (class "Default")
      (node (ref "RJ1") (pin "7") (pinfunction "7_7") (pintype "unspecified"))
    )
    (net (code "49") (name "unconnected-(RJ1-Pad8)") (class "Default")
      (node (ref "RJ1") (pin "8") (pinfunction "8_8") (pintype "unspecified"))
    )
    (net (code "50") (name "unconnected-(U1-2-Pad5)") (class "Default")
      (node (ref "U1") (pin "5") (pinfunction "2_5") (pintype "unspecified"))
    )
    (net (code "51") (name "unconnected-(U1-4-Pad7)") (class "Default")
      (node (ref "U1") (pin "7") (pinfunction "4_7") (pintype "unspecified"))
    )
    (net (code "52") (name "unconnected-(U1-12-Pad15)") (class "Default")
      (node (ref "U1") (pin "15") (pinfunction "12_15") (pintype "unspecified"))
    )
    (net (code "53") (name "unconnected-(U1-13-Pad16)") (class "Default")
      (node (ref "U1") (pin "16") (pinfunction "13_16") (pintype "unspecified"))
    )
    (net (code "54") (name "unconnected-(U1-A3-Pad20)") (class "Default")
      (node (ref "U1") (pin "20") (pinfunction "A3_20") (pintype "unspecified"))
    )
    (net (code "55") (name "unconnected-(U1-RAW-Pad24)") (class "Default")
      (node (ref "U1") (pin "24") (pinfunction "RAW_24") (pintype "unspecified"))
    )
    (net (code "56") (name "unconnected-(U1-RST-Pad3)") (class "Default")
      (node (ref "U1") (pin "3") (pinfunction "RST_3") (pintype "unspecified"))
    )
    (net (code "57") (name "unconnected-(U1-RST-Pad22)") (class "Default")
      (node (ref "U1") (pin "22") (pinfunction "RST_22") (pintype "unspecified"))
    )
  )
)
